# Morpheus_pill.net
KiCad netlist of a schematic drawn in Altium Designer
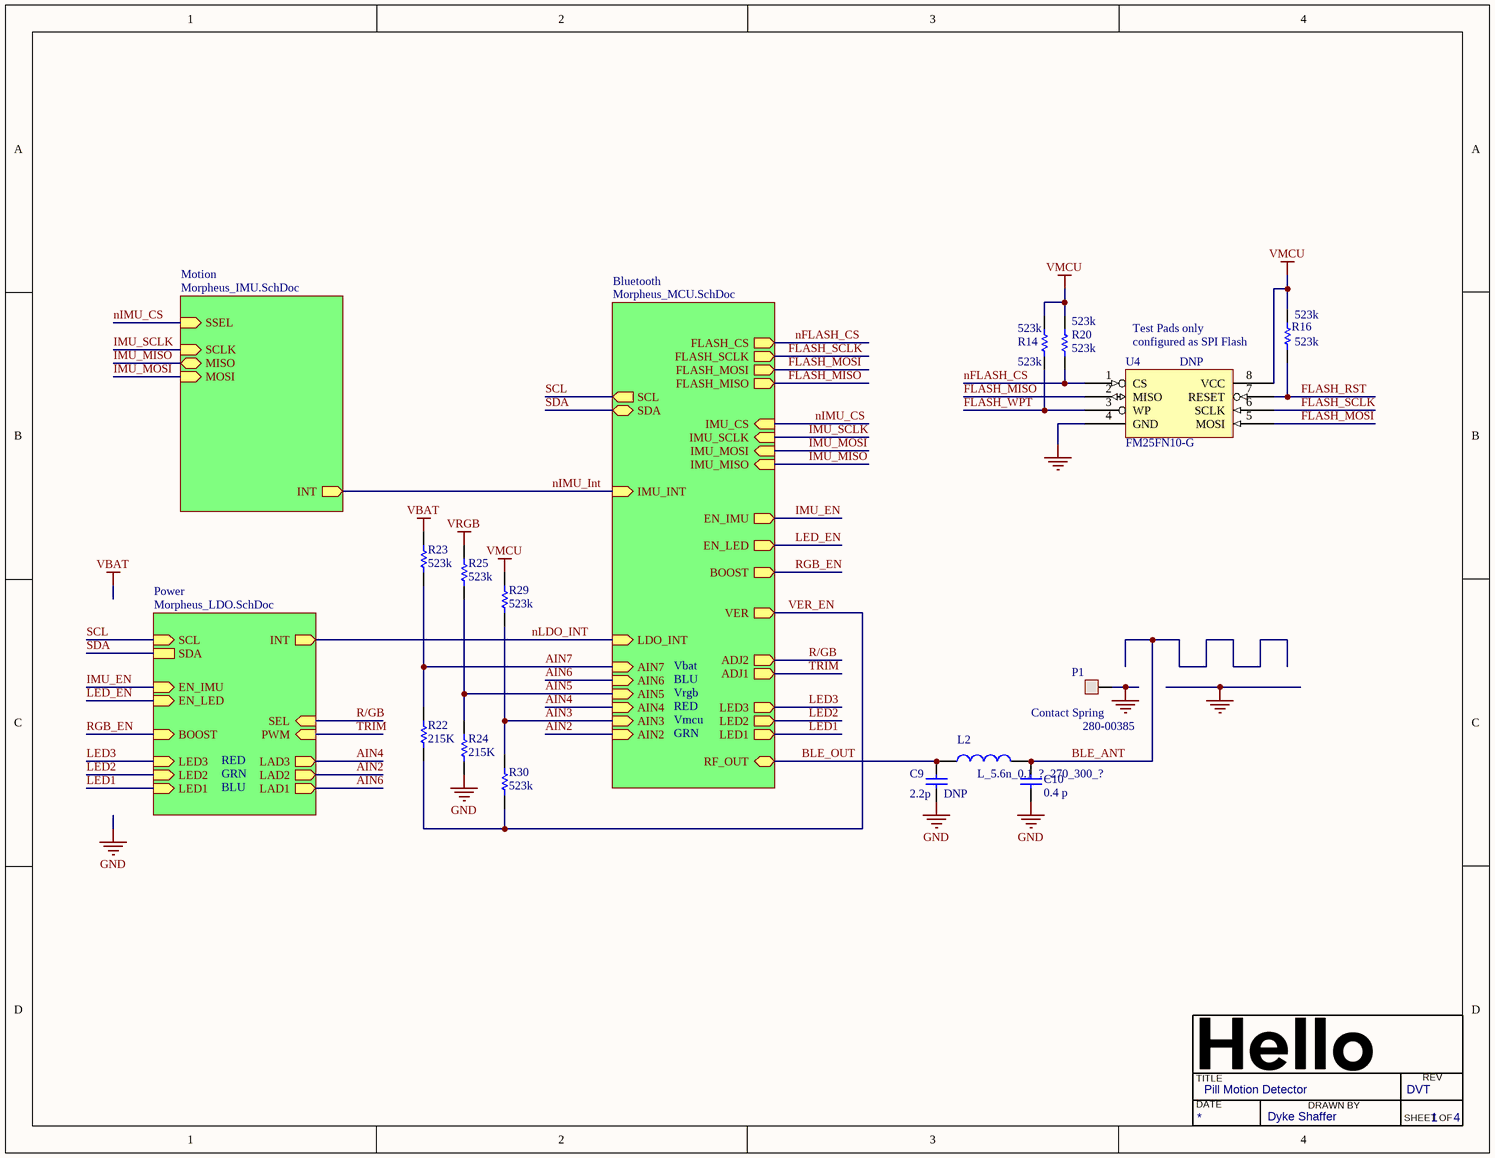
[diagram p0: Morpheus_pill.SchDoc]

(export (version "E")
  (design (tool "Eeschema 10.0.6"))
  (components
    (comp (ref "C9")
      (value "DNP")
      (footprint "CAP0201_SENSE_DVT")
      (description "Chip capacitor")
      (fields
        (field (name "ALTIUM_VALUE") "2.2p")
        (field (name "TOLERANCE") "5%")
        (field (name "VOLTAGE") "25V")
      )
      (libsource (lib "Morpheus_pill") (part "C_2.2p_5_25_C0G_0201"))
    )
    (comp (ref "C10")
      (value "0.4 p")
      (footprint "CAP0201_SENSE_DVT")
      (description "CAP CER 0.4PF 25V NP0 0201")
      (fields (field (name "TOLERANCE") "5 %") (field (name "VOLTAGE") "25 V"))
      (libsource (lib "Morpheus_pill") (part "C_0.4p_5_25_NP0_0201"))
    )
    (comp (ref "L2")
      (value "L_5.6n_0.1_?_270_300_?")
      (footprint "IND_0402")
      (description "SMD RF inductor 2.2nH")
      (fields (field (name "TOLERANCE") "0.1"))
      (libsource (lib "Morpheus_pill") (part "L_5.6n_0.1_?_270_300_?"))
    )
    (comp (ref "P1")
      (value "Contact Spring")
      (footprint "TP120X70SC")
      (description "3100069=SEALEDFINGR1715EMBOS")
      (fields (field (name "HELLO_PN") "280-00385"))
      (libsource (lib "Morpheus_pill") (part "TP-120X70-SC"))
    )
    (comp (ref "R14")
      (value "523k")
      (footprint "RES0402_SENSE_DVT")
      (description "RES 523K OHM 1/10W 1% 0402 SMD")
      (fields
        (field (name "ALTIUM_VALUE") "523k")
        (field (name "TOLERANCE") "1 %")
        (field (name "POWER") "0.1 W")
      )
      (libsource (lib "Morpheus_pill") (part "R_523k_1_0.1_0402"))
    )
    (comp (ref "R16")
      (value "523k")
      (footprint "RES0402_SENSE_DVT")
      (description "RES 523K OHM 1/10W 1% 0402 SMD")
      (fields
        (field (name "ALTIUM_VALUE") "523k")
        (field (name "TOLERANCE") "1 %")
        (field (name "POWER") "0.1 W")
      )
      (libsource (lib "Morpheus_pill") (part "R_523k_1_0.1_0402"))
    )
    (comp (ref "R20")
      (value "523k")
      (footprint "RES0402_SENSE_DVT")
      (description "RES 523K OHM 1/10W 1% 0402 SMD")
      (fields
        (field (name "ALTIUM_VALUE") "523k")
        (field (name "TOLERANCE") "1 %")
        (field (name "POWER") "0.1 W")
      )
      (libsource (lib "Morpheus_pill") (part "R_523k_1_0.1_0402"))
    )
    (comp (ref "R22")
      (value "215K")
      (footprint "RES0402_SENSE_DVT")
      (description "RES 215K OHM 1/10W 1% 0402 SMD")
      (fields (field (name "TOLERANCE") "1 %") (field (name "POWER") "0.1 W"))
      (libsource (lib "Morpheus_pill") (part "R_215K_1_0.1_0402"))
    )
    (comp (ref "R23")
      (value "523k")
      (footprint "RES0402_SENSE_DVT")
      (description "RES 523K OHM 1/10W 1% 0402 SMD")
      (fields (field (name "TOLERANCE") "1 %") (field (name "POWER") "0.1 W"))
      (libsource (lib "Morpheus_pill") (part "R_523k_1_0.1_0402"))
    )
    (comp (ref "R24")
      (value "215K")
      (footprint "RES0402_SENSE_DVT")
      (description "RES 215K OHM 1/10W 1% 0402 SMD")
      (fields (field (name "TOLERANCE") "1 %") (field (name "POWER") "0.1 W"))
      (libsource (lib "Morpheus_pill") (part "R_215K_1_0.1_0402"))
    )
    (comp (ref "R25")
      (value "523k")
      (footprint "RES0402_SENSE_DVT")
      (description "RES 523K OHM 1/10W 1% 0402 SMD")
      (fields (field (name "TOLERANCE") "1 %") (field (name "POWER") "0.1 W"))
      (libsource (lib "Morpheus_pill") (part "R_523k_1_0.1_0402"))
    )
    (comp (ref "R29")
      (value "523k")
      (footprint "RES0402_SENSE_DVT")
      (description "RES 523K OHM 1/10W 1% 0402 SMD")
      (fields (field (name "TOLERANCE") "1 %") (field (name "POWER") "0.1 W"))
      (libsource (lib "Morpheus_pill") (part "R_523k_1_0.1_0402"))
    )
    (comp (ref "R30")
      (value "523k")
      (footprint "RES0402_SENSE_DVT")
      (description "RES 523K OHM 1/10W 1% 0402 SMD")
      (fields (field (name "TOLERANCE") "1 %") (field (name "POWER") "0.1 W"))
      (libsource (lib "Morpheus_pill") (part "R_523k_1_0.1_0402"))
    )
    (comp (ref "U4")
      (value "DNP")
      (footprint "DFN127P600x500x80-8D")
      (description "Cypress SPI FRAM 128Kx8")
      (fields (field (name "PN") "FM25FN10-G"))
      (libsource (lib "Morpheus_pill") (part "FM25VN10-G"))
    )
  )
  (nets
    (net (code "2") (name "/AIN3") (class "Default")
      (node (ref "R29") (pin "1") (pinfunction "1_1") (pintype "passive"))
      (node (ref "R30") (pin "2") (pinfunction "2_2") (pintype "passive"))
    )
    (net (code "4") (name "/AIN5") (class "Default")
      (node (ref "R24") (pin "2") (pinfunction "2_2") (pintype "passive"))
      (node (ref "R25") (pin "1") (pinfunction "1_1") (pintype "passive"))
    )
    (net (code "6") (name "/AIN7") (class "Default")
      (node (ref "R22") (pin "2") (pinfunction "2_2") (pintype "passive"))
      (node (ref "R23") (pin "1") (pinfunction "1_1") (pintype "passive"))
    )
    (net (code "7") (name "/BLE_ANT") (class "Default")
      (node (ref "C10") (pin "1") (pinfunction "1_1") (pintype "passive"))
      (node (ref "L2") (pin "2") (pintype "passive"))
    )
    (net (code "8") (name "/BLE_OUT") (class "Default")
      (node (ref "C9") (pin "1") (pinfunction "1_1") (pintype "passive"))
      (node (ref "L2") (pin "1") (pintype "passive"))
    )
    (net (code "9") (name "/FLASH_MISO") (class "Default")
      (node (ref "U4") (pin "2") (pinfunction "MISO_2") (pintype "bidirectional"))
    )
    (net (code "10") (name "/FLASH_MOSI") (class "Default")
      (node (ref "U4") (pin "5") (pinfunction "MOSI_5") (pintype "input"))
    )
    (net (code "11") (name "/FLASH_RST") (class "Default")
      (node (ref "R16") (pin "1") (pinfunction "1_1") (pintype "passive"))
      (node (ref "U4") (pin "7") (pinfunction "RESET_7") (pintype "input"))
    )
    (net (code "12") (name "/FLASH_SCLK") (class "Default")
      (node (ref "U4") (pin "6") (pinfunction "SCLK_6") (pintype "input"))
    )
    (net (code "13") (name "/FLASH_WPT") (class "Default")
      (node (ref "R14") (pin "1") (pinfunction "1_1") (pintype "passive"))
      (node (ref "U4") (pin "3") (pinfunction "WP_3") (pintype "passive"))
    )
    (net (code "27") (name "/VER_EN") (class "Default")
      (node (ref "R22") (pin "1") (pinfunction "1_1") (pintype "passive"))
      (node (ref "R30") (pin "1") (pinfunction "1_1") (pintype "passive"))
    )
    (net (code "28") (name "/nFLASH_CS") (class "Default")
      (node (ref "R20") (pin "1") (pinfunction "1_1") (pintype "passive"))
      (node (ref "U4") (pin "1") (pinfunction "CS_1") (pintype "input"))
    )
    (net (code "32") (name "GND") (class "Default")
      (node (ref "C10") (pin "2") (pinfunction "2_2") (pintype "passive"))
      (node (ref "C9") (pin "2") (pinfunction "2_2") (pintype "passive"))
      (node (ref "P1") (pin "1") (pinfunction "1_1") (pintype "passive"))
      (node (ref "R24") (pin "1") (pinfunction "1_1") (pintype "passive"))
      (node (ref "U4") (pin "4") (pinfunction "GND_4") (pintype "power_in"))
    )
    (net (code "33") (name "VBAT") (class "Default")
      (node (ref "R23") (pin "2") (pinfunction "2_2") (pintype "passive"))
    )
    (net (code "34") (name "VMCU") (class "Default")
      (node (ref "R14") (pin "2") (pinfunction "2_2") (pintype "passive"))
      (node (ref "R16") (pin "2") (pinfunction "2_2") (pintype "passive"))
      (node (ref "R20") (pin "2") (pinfunction "2_2") (pintype "passive"))
      (node (ref "R29") (pin "2") (pinfunction "2_2") (pintype "passive"))
      (node (ref "U4") (pin "8") (pinfunction "VCC_8") (pintype "power_in"))
    )
    (net (code "35") (name "VRGB") (class "Default")
      (node (ref "R25") (pin "2") (pinfunction "2_2") (pintype "passive"))
    )
  )
)
